# POWER.net
KiCad netlist of a schematic drawn in Altium Designer
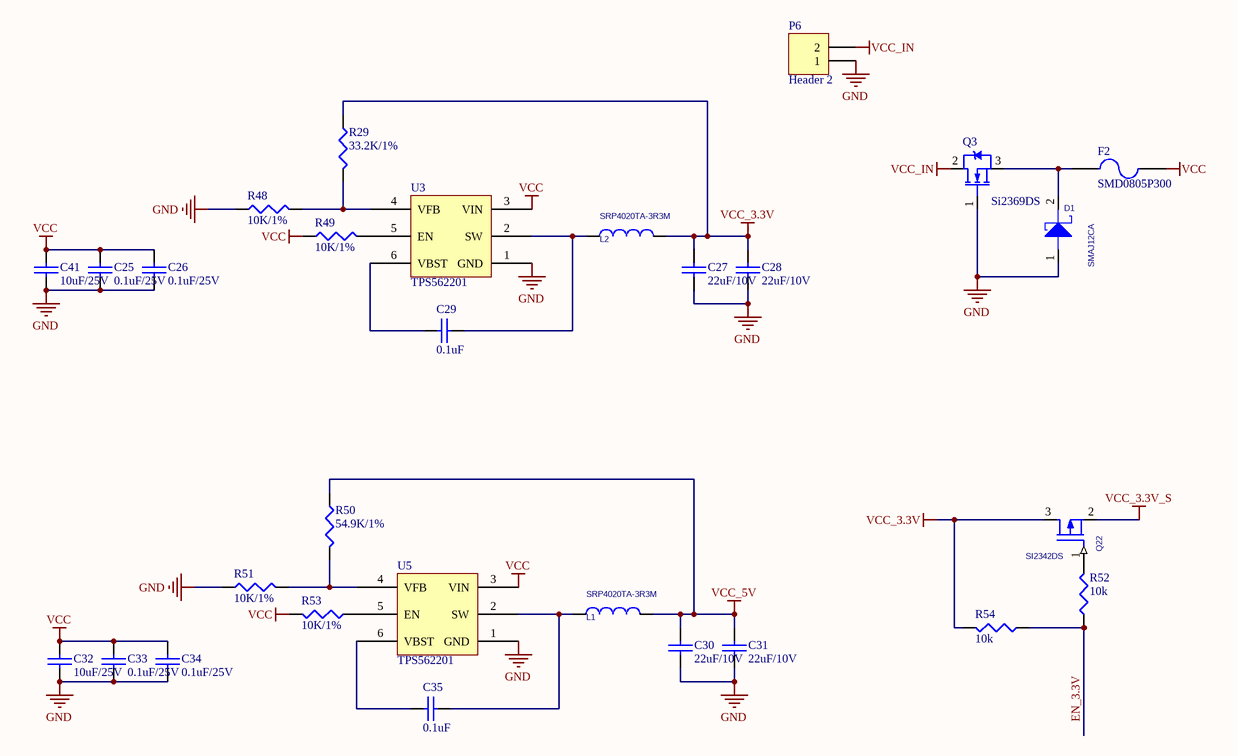
[diagram p0: POWER.SchDoc]

(export (version "E")
  (design (tool "Eeschema 10.0.6"))
  (components
    (comp (ref "C25")
      (value "0.1uF/25V")
      (footprint "0603C")
      (description "Capacitor")
      (libsource (lib "ZWLIntegrated_Library") (part "CAP"))
    )
    (comp (ref "C26")
      (value "0.1uF/25V")
      (footprint "0603C")
      (description "Capacitor")
      (libsource (lib "ZWLIntegrated_Library") (part "CAP"))
    )
    (comp (ref "C27")
      (value "22uF/10V")
      (footprint "1206C")
      (description "Capacitor")
      (libsource (lib "ZWLIntegrated_Library") (part "CAP"))
    )
    (comp (ref "C28")
      (value "22uF/10V")
      (footprint "1206C")
      (description "Capacitor")
      (libsource (lib "ZWLIntegrated_Library") (part "CAP"))
    )
    (comp (ref "C29")
      (value "0.1uF")
      (footprint "0603C")
      (description "Capacitor")
      (libsource (lib "ZWLIntegrated_Library") (part "CAP"))
    )
    (comp (ref "C30")
      (value "22uF/10V")
      (footprint "1206C")
      (description "Capacitor")
      (libsource (lib "ZWLIntegrated_Library") (part "CAP"))
    )
    (comp (ref "C31")
      (value "22uF/10V")
      (footprint "1206C")
      (description "Capacitor")
      (libsource (lib "ZWLIntegrated_Library") (part "CAP"))
    )
    (comp (ref "C32")
      (value "10uF/25V")
      (footprint "0603C")
      (description "Capacitor")
      (libsource (lib "ZWLIntegrated_Library") (part "CAP"))
    )
    (comp (ref "C33")
      (value "0.1uF/25V")
      (footprint "0603C")
      (description "Capacitor")
      (libsource (lib "ZWLIntegrated_Library") (part "CAP"))
    )
    (comp (ref "C34")
      (value "0.1uF/25V")
      (footprint "0603C")
      (description "Capacitor")
      (libsource (lib "ZWLIntegrated_Library") (part "CAP"))
    )
    (comp (ref "C35")
      (value "0.1uF")
      (footprint "0603C")
      (description "Capacitor")
      (libsource (lib "ZWLIntegrated_Library") (part "CAP"))
    )
    (comp (ref "C41")
      (value "10uF/25V")
      (footprint "0603C")
      (description "Capacitor")
      (libsource (lib "ZWLIntegrated_Library") (part "CAP"))
    )
    (comp (ref "D1")
      (value "SMAJ12CA")
      (footprint "SMA")
      (libsource (lib "KT_iBeacon") (part "DIODE_SCHOTTKY_0"))
    )
    (comp (ref "F2")
      (value "SMD0805P300")
      (footprint "0805R")
      (description "Fuse")
      (fields (field (name "PUBLISHER") "Altium Limited"))
      (libsource (lib "Miscellaneous Devices") (part "Fuse 2"))
    )
    (comp (ref "L1") (value "SRP4020TA-3R3M") (footprint "CD_4*4") (libsource (lib "*") (part "INDUCTOR_1")))
    (comp (ref "L2") (value "SRP4020TA-3R3M") (footprint "CD_4*4") (libsource (lib "*") (part "INDUCTOR_1")))
    (comp (ref "P6")
      (value "Header 2")
      (footprint "2X2.54MMZ")
      (description "Header, 2-Pin")
      (fields (field (name "PUBLISHER") "Altium Limited"))
      (libsource (lib "Miscellaneous Connectors") (part "Header 2"))
    )
    (comp (ref "Q3")
      (value "Si2369DS")
      (footprint "sot23-3")
      (description "NMOSFET")
      (libsource (lib "SM") (part "NCE4060K"))
    )
    (comp (ref "Q22") (value "SI2342DS") (footprint "SOT23") (libsource (lib "*") (part "MOSFET P_1")))
    (comp (ref "R29")
      (value "33.2K/1%")
      (footprint "0603R")
      (libsource (lib "ZWLIntegrated_Library") (part "RES1"))
    )
    (comp (ref "R48")
      (value "10K/1%")
      (footprint "0603R")
      (libsource (lib "ZWLIntegrated_Library") (part "RES1"))
    )
    (comp (ref "R49")
      (value "10K/1%")
      (footprint "0603R")
      (libsource (lib "ZWLIntegrated_Library") (part "RES1"))
    )
    (comp (ref "R50")
      (value "54.9K/1%")
      (footprint "0603R")
      (libsource (lib "ZWLIntegrated_Library") (part "RES1"))
    )
    (comp (ref "R51")
      (value "10K/1%")
      (footprint "0603R")
      (libsource (lib "ZWLIntegrated_Library") (part "RES1"))
    )
    (comp (ref "R52")
      (value "10k")
      (footprint "0603R")
      (libsource (lib "ZWLIntegrated_Library") (part "RES1"))
    )
    (comp (ref "R53")
      (value "10K/1%")
      (footprint "0603R")
      (libsource (lib "ZWLIntegrated_Library") (part "RES1"))
    )
    (comp (ref "R54")
      (value "10k")
      (footprint "0603R")
      (libsource (lib "ZWLIntegrated_Library") (part "RES1"))
    )
    (comp (ref "U3")
      (value "TPS562201")
      (footprint "SOT-23-6")
      (libsource (lib "Schlib_20110825") (part "TPS562201"))
    )
    (comp (ref "U5")
      (value "TPS562201")
      (footprint "SOT-23-6")
      (libsource (lib "Schlib_20110825") (part "TPS562201"))
    )
  )
  (nets
    (net (code "1") (name "/EN_3.3V") (class "Default")
      (node (ref "R52") (pin "1") (pinfunction "1_1") (pintype "passive"))
      (node (ref "R54") (pin "1") (pinfunction "1_1") (pintype "passive"))
    )
    (net (code "2") (name "GND") (class "Default")
      (node (ref "C25") (pin "1") (pinfunction "1_1") (pintype "passive"))
      (node (ref "C26") (pin "1") (pinfunction "1_1") (pintype "passive"))
      (node (ref "C27") (pin "2") (pinfunction "2_2") (pintype "passive"))
      (node (ref "C28") (pin "2") (pinfunction "2_2") (pintype "passive"))
      (node (ref "C30") (pin "2") (pinfunction "2_2") (pintype "passive"))
      (node (ref "C31") (pin "2") (pinfunction "2_2") (pintype "passive"))
      (node (ref "C32") (pin "1") (pinfunction "1_1") (pintype "passive"))
      (node (ref "C33") (pin "1") (pinfunction "1_1") (pintype "passive"))
      (node (ref "C34") (pin "1") (pinfunction "1_1") (pintype "passive"))
      (node (ref "C41") (pin "1") (pinfunction "1_1") (pintype "passive"))
      (node (ref "D1") (pin "1") (pinfunction "1_1") (pintype "passive"))
      (node (ref "P6") (pin "1") (pinfunction "1_1") (pintype "passive"))
      (node (ref "Q3") (pin "1") (pinfunction "G_1") (pintype "passive"))
      (node (ref "R48") (pin "1") (pinfunction "1_1") (pintype "passive"))
      (node (ref "R51") (pin "1") (pinfunction "1_1") (pintype "passive"))
      (node (ref "U3") (pin "1") (pinfunction "GND_1") (pintype "passive"))
      (node (ref "U5") (pin "1") (pinfunction "GND_1") (pintype "passive"))
    )
    (net (code "3") (name "Net-(Q3-S)") (class "Default")
      (node (ref "D1") (pin "2") (pinfunction "2_2") (pintype "passive"))
      (node (ref "F2") (pin "1") (pinfunction "1_1") (pintype "passive"))
      (node (ref "Q3") (pin "3") (pinfunction "S_3") (pintype "passive"))
    )
    (net (code "4") (name "Net-(Q22-GATE)") (class "Default")
      (node (ref "Q22") (pin "1") (pinfunction "GATE_1") (pintype "input"))
      (node (ref "R52") (pin "2") (pinfunction "2_2") (pintype "passive"))
    )
    (net (code "5") (name "Net-(U3-EN)") (class "Default")
      (node (ref "R49") (pin "2") (pinfunction "2_2") (pintype "passive"))
      (node (ref "U3") (pin "5") (pinfunction "EN_5") (pintype "passive"))
    )
    (net (code "6") (name "Net-(U3-SW)") (class "Default")
      (node (ref "C29") (pin "1") (pinfunction "1_1") (pintype "passive"))
      (node (ref "L2") (pin "1") (pinfunction "1_1") (pintype "passive"))
      (node (ref "U3") (pin "2") (pinfunction "SW_2") (pintype "passive"))
    )
    (net (code "7") (name "Net-(U3-VBST)") (class "Default")
      (node (ref "C29") (pin "2") (pinfunction "2_2") (pintype "passive"))
      (node (ref "U3") (pin "6") (pinfunction "VBST_6") (pintype "passive"))
    )
    (net (code "8") (name "Net-(U3-VFB)") (class "Default")
      (node (ref "R29") (pin "2") (pinfunction "2_2") (pintype "passive"))
      (node (ref "R48") (pin "2") (pinfunction "2_2") (pintype "passive"))
      (node (ref "U3") (pin "4") (pinfunction "VFB_4") (pintype "passive"))
    )
    (net (code "9") (name "Net-(U5-EN)") (class "Default")
      (node (ref "R53") (pin "1") (pinfunction "1_1") (pintype "passive"))
      (node (ref "U5") (pin "5") (pinfunction "EN_5") (pintype "passive"))
    )
    (net (code "10") (name "Net-(U5-SW)") (class "Default")
      (node (ref "C35") (pin "1") (pinfunction "1_1") (pintype "passive"))
      (node (ref "L1") (pin "1") (pinfunction "1_1") (pintype "passive"))
      (node (ref "U5") (pin "2") (pinfunction "SW_2") (pintype "passive"))
    )
    (net (code "11") (name "Net-(U5-VBST)") (class "Default")
      (node (ref "C35") (pin "2") (pinfunction "2_2") (pintype "passive"))
      (node (ref "U5") (pin "6") (pinfunction "VBST_6") (pintype "passive"))
    )
    (net (code "12") (name "Net-(U5-VFB)") (class "Default")
      (node (ref "R50") (pin "2") (pinfunction "2_2") (pintype "passive"))
      (node (ref "R51") (pin "2") (pinfunction "2_2") (pintype "passive"))
      (node (ref "U5") (pin "4") (pinfunction "VFB_4") (pintype "passive"))
    )
    (net (code "13") (name "VCC") (class "Default")
      (node (ref "C25") (pin "2") (pinfunction "2_2") (pintype "passive"))
      (node (ref "C26") (pin "2") (pinfunction "2_2") (pintype "passive"))
      (node (ref "C32") (pin "2") (pinfunction "2_2") (pintype "passive"))
      (node (ref "C33") (pin "2") (pinfunction "2_2") (pintype "passive"))
      (node (ref "C34") (pin "2") (pinfunction "2_2") (pintype "passive"))
      (node (ref "C41") (pin "2") (pinfunction "2_2") (pintype "passive"))
      (node (ref "F2") (pin "2") (pinfunction "2_2") (pintype "passive"))
      (node (ref "R49") (pin "1") (pinfunction "1_1") (pintype "passive"))
      (node (ref "R53") (pin "2") (pinfunction "2_2") (pintype "passive"))
      (node (ref "U3") (pin "3") (pinfunction "VIN_3") (pintype "passive"))
      (node (ref "U5") (pin "3") (pinfunction "VIN_3") (pintype "passive"))
    )
    (net (code "14") (name "VCC_3.3V") (class "Default")
      (node (ref "C27") (pin "1") (pinfunction "1_1") (pintype "passive"))
      (node (ref "C28") (pin "1") (pinfunction "1_1") (pintype "passive"))
      (node (ref "L2") (pin "2") (pinfunction "2_2") (pintype "passive"))
      (node (ref "Q22") (pin "3") (pinfunction "SOURCE_3") (pintype "passive"))
      (node (ref "R29") (pin "1") (pinfunction "1_1") (pintype "passive"))
      (node (ref "R54") (pin "2") (pinfunction "2_2") (pintype "passive"))
    )
    (net (code "15") (name "VCC_3.3V_S") (class "Default")
      (node (ref "Q22") (pin "2") (pinfunction "DRAIN_2") (pintype "passive"))
    )
    (net (code "16") (name "VCC_5V") (class "Default")
      (node (ref "C30") (pin "1") (pinfunction "1_1") (pintype "passive"))
      (node (ref "C31") (pin "1") (pinfunction "1_1") (pintype "passive"))
      (node (ref "L1") (pin "2") (pinfunction "2_2") (pintype "passive"))
      (node (ref "R50") (pin "1") (pinfunction "1_1") (pintype "passive"))
    )
    (net (code "17") (name "VCC_IN") (class "Default")
      (node (ref "P6") (pin "2") (pinfunction "2_2") (pintype "passive"))
      (node (ref "Q3") (pin "2") (pinfunction "D_2") (pintype "passive"))
    )
  )
)
